# doorduino3.net
KiCad netlist of a schematic drawn in EAGLE
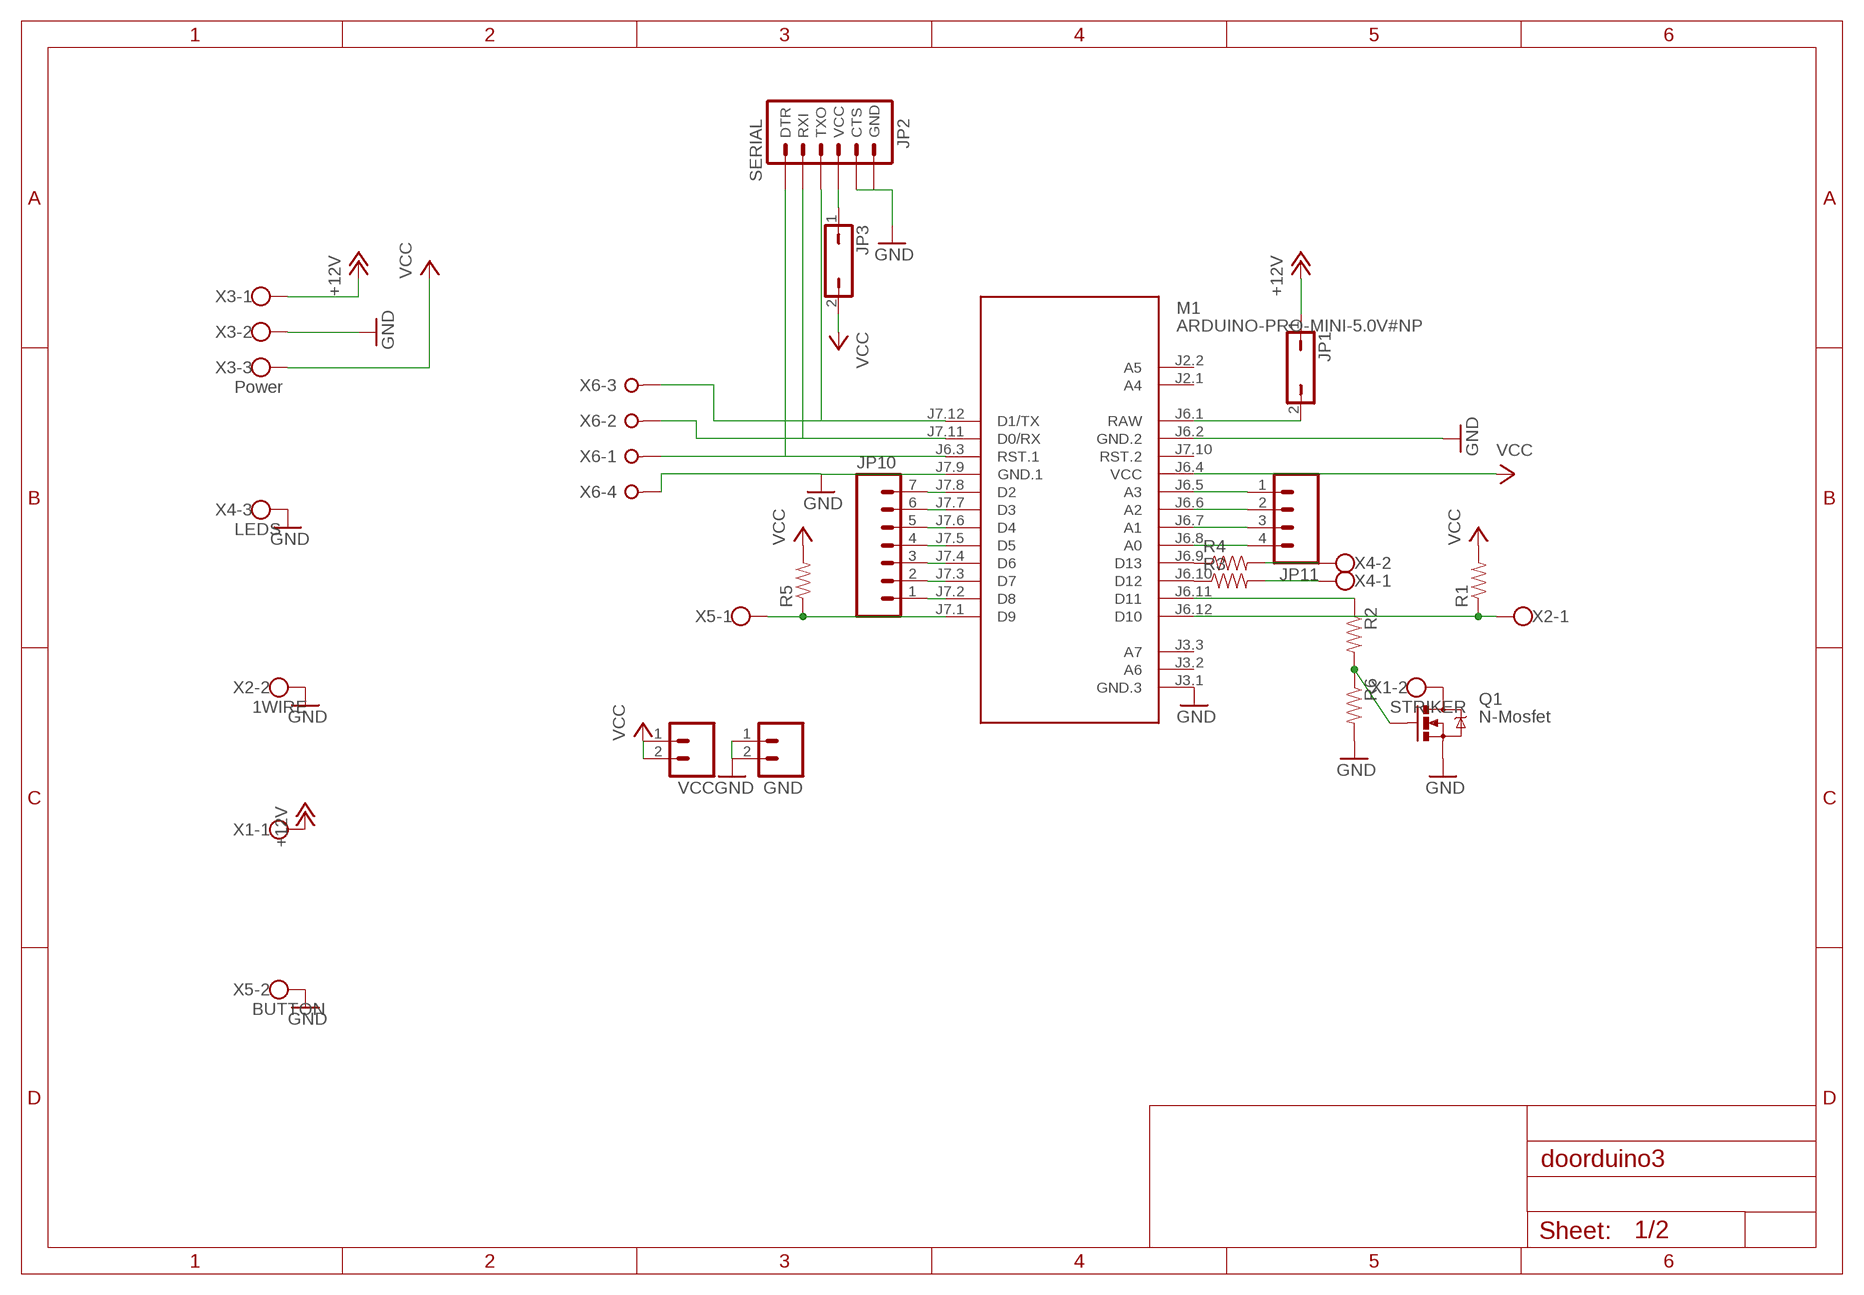
[diagram p0: schematic, sheet 1]
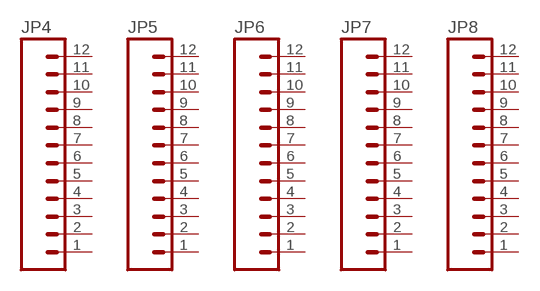
[diagram p1: schematic, sheet 2]

(export (version "E")
  (design (tool "Eeschema 10.0.6"))
  (components
    (comp (ref "JP4")
      (value "M12NO_SILK")
      (footprint "eagle-import:1X12_NO_SILK")
      (libsource (lib "eagle-import") (part "M12NO_SILK"))
    )
    (comp (ref "JP5")
      (value "M12NO_SILK")
      (footprint "eagle-import:1X12_NO_SILK")
      (libsource (lib "eagle-import") (part "M12NO_SILK"))
    )
    (comp (ref "JP6")
      (value "M12NO_SILK")
      (footprint "eagle-import:1X12_NO_SILK")
      (libsource (lib "eagle-import") (part "M12NO_SILK"))
    )
    (comp (ref "JP7")
      (value "M12NO_SILK")
      (footprint "eagle-import:1X12_NO_SILK")
      (libsource (lib "eagle-import") (part "M12NO_SILK"))
    )
    (comp (ref "JP8")
      (value "M12NO_SILK")
      (footprint "eagle-import:1X12_NO_SILK")
      (libsource (lib "eagle-import") (part "M12NO_SILK"))
    )
    (comp (ref "GND")
      (value "M021X02_NO_SILK")
      (footprint "eagle-import:1X02_NO_SILK")
      (libsource (lib "eagle-import") (part "M021X02_NO_SILK"))
    )
    (comp (ref "JP1")
      (value "JP1Q")
      (footprint "eagle-import:JP1")
      (libsource (lib "eagle-import") (part "JP1Q"))
    )
    (comp (ref "JP2")
      (value "SERIAL")
      (footprint "eagle-import:1X06_LONGPADS")
      (libsource (lib "eagle-import") (part "ARDUINO_SERIAL_PROGRAMLONGPADS"))
    )
    (comp (ref "JP3")
      (value "JP1Q")
      (footprint "eagle-import:JP1")
      (libsource (lib "eagle-import") (part "JP1Q"))
    )
    (comp (ref "JP10")
      (value "M07")
      (footprint "eagle-import:1X07")
      (libsource (lib "eagle-import") (part "M07"))
    )
    (comp (ref "JP11")
      (value "M04NO_SILK_ALL_ROUND")
      (footprint "eagle-import:1X04_NO_SILK_ALL_ROUND")
      (libsource (lib "eagle-import") (part "M04NO_SILK_ALL_ROUND"))
    )
    (comp (ref "M1")
      (value "ARDUINO-PRO-MINI-5.0V#NP")
      (footprint "eagle-import:ARDUINO-PRO-MINI#NP")
      (libsource (lib "eagle-import") (part "ARDUINO-PRO-MINI-#NP5.0V"))
    )
    (comp (ref "Q1")
      (value "N-Mosfet")
      (footprint "eagle-import:TO220V")
      (libsource (lib "eagle-import") (part "MOSFET-NCHANNELFQP30N06L"))
    )
    (comp (ref "R1")
      (value "RESISTOR0805-RES")
      (footprint "eagle-import:0805")
      (libsource (lib "eagle-import") (part "RESISTOR0805-RES"))
    )
    (comp (ref "R2")
      (value "RESISTOR0805-RES")
      (footprint "eagle-import:0805")
      (libsource (lib "eagle-import") (part "RESISTOR0805-RES"))
    )
    (comp (ref "R3")
      (value "RESISTOR0805-RES")
      (footprint "eagle-import:0805")
      (libsource (lib "eagle-import") (part "RESISTOR0805-RES"))
    )
    (comp (ref "R4")
      (value "RESISTOR0805-RES")
      (footprint "eagle-import:0805")
      (libsource (lib "eagle-import") (part "RESISTOR0805-RES"))
    )
    (comp (ref "R5")
      (value "RESISTOR0805-RES")
      (footprint "eagle-import:0805")
      (libsource (lib "eagle-import") (part "RESISTOR0805-RES"))
    )
    (comp (ref "R6")
      (value "RESISTOR0805-RES")
      (footprint "eagle-import:0805")
      (libsource (lib "eagle-import") (part "RESISTOR0805-RES"))
    )
    (comp (ref "VCC")
      (value "M021X02_NO_SILK")
      (footprint "eagle-import:1X02_NO_SILK")
      (libsource (lib "eagle-import") (part "M021X02_NO_SILK"))
    )
    (comp (ref "X1")
      (value "STRIKER")
      (footprint "eagle-import:W237-102")
      (fields (field (name "MPN") "237-102"))
      (libsource (lib "eagle-import") (part "W237-102"))
    )
    (comp (ref "X2")
      (value "1WIRE")
      (footprint "eagle-import:W237-102")
      (fields (field (name "MPN") "237-102"))
      (libsource (lib "eagle-import") (part "W237-102"))
    )
    (comp (ref "X3")
      (value "Power")
      (footprint "eagle-import:W237-103")
      (fields (field (name "MPN") "237-103"))
      (libsource (lib "eagle-import") (part "W237-103"))
    )
    (comp (ref "X4")
      (value "LEDS")
      (footprint "eagle-import:W237-103")
      (fields (field (name "MPN") "237-103"))
      (libsource (lib "eagle-import") (part "W237-103"))
    )
    (comp (ref "X5")
      (value "BUTTON")
      (footprint "eagle-import:W237-102")
      (fields (field (name "MPN") "237-102"))
      (libsource (lib "eagle-import") (part "W237-102"))
    )
    (comp (ref "X6")
      (value "W237-04P")
      (footprint "eagle-import:W237-4P")
      (libsource (lib "eagle-import") (part "W237-04P"))
    )
  )
  (nets
    (net (code "1") (name "+12V") (class "Default")
      (node (ref "JP1") (pin "1") (pinfunction "1_1") (pintype "passive"))
      (node (ref "X1") (pin "1") (pinfunction "KL_1") (pintype "passive"))
      (node (ref "X3") (pin "1") (pinfunction "KL_1") (pintype "passive"))
    )
    (net (code "2") (name "GND") (class "Default")
      (node (ref "GND") (pin "1") (pinfunction "1_1") (pintype "passive"))
      (node (ref "GND") (pin "2") (pinfunction "2_2") (pintype "passive"))
      (node (ref "JP2") (pin "5") (pinfunction "CTS_5") (pintype "passive"))
      (node (ref "JP2") (pin "6") (pinfunction "GND_6") (pintype "passive"))
      (node (ref "M1") (pin "J3.1") (pinfunction "GND.3_J3.1") (pintype "bidirectional"))
      (node (ref "M1") (pin "J6.2") (pinfunction "GND.2_J6.2") (pintype "power_in"))
      (node (ref "M1") (pin "J7.9") (pinfunction "GND.1_J7.9") (pintype "power_in"))
      (node (ref "Q1") (pin "3") (pinfunction "S_3") (pintype "passive"))
      (node (ref "R6") (pin "2") (pinfunction "2_2") (pintype "passive"))
      (node (ref "X2") (pin "2") (pinfunction "KL_2") (pintype "passive"))
      (node (ref "X3") (pin "2") (pinfunction "KL_2") (pintype "passive"))
      (node (ref "X4") (pin "3") (pinfunction "KL_3") (pintype "passive"))
      (node (ref "X5") (pin "2") (pinfunction "KL_2") (pintype "passive"))
      (node (ref "X6") (pin "4") (pinfunction "KL_4") (pintype "passive"))
    )
    (net (code "3") (name "Net-(JP2-DTR)") (class "Default")
      (node (ref "JP2") (pin "1") (pinfunction "DTR_1") (pintype "passive"))
      (node (ref "M1") (pin "J6.3") (pinfunction "RST.1_J6.3") (pintype "bidirectional"))
      (node (ref "X6") (pin "1") (pinfunction "KL_1") (pintype "passive"))
    )
    (net (code "4") (name "Net-(JP2-RXI)") (class "Default")
      (node (ref "JP2") (pin "2") (pinfunction "RXI_2") (pintype "passive"))
      (node (ref "M1") (pin "J7.11") (pinfunction "D0/RX_J7.11") (pintype "bidirectional"))
      (node (ref "X6") (pin "2") (pinfunction "KL_2") (pintype "passive"))
    )
    (net (code "5") (name "Net-(JP2-TXO)") (class "Default")
      (node (ref "JP2") (pin "3") (pinfunction "TXO_3") (pintype "passive"))
      (node (ref "M1") (pin "J7.12") (pinfunction "D1/TX_J7.12") (pintype "bidirectional"))
      (node (ref "X6") (pin "3") (pinfunction "KL_3") (pintype "passive"))
    )
    (net (code "6") (name "Net-(JP2-VCC)") (class "Default")
      (node (ref "JP2") (pin "4") (pinfunction "VCC_4") (pintype "passive"))
      (node (ref "JP3") (pin "1") (pinfunction "1_1") (pintype "passive"))
    )
    (net (code "7") (name "Net-(M1-A0)") (class "Default")
      (node (ref "JP11") (pin "4") (pinfunction "4_4") (pintype "passive"))
      (node (ref "M1") (pin "J6.8") (pinfunction "A0_J6.8") (pintype "bidirectional"))
    )
    (net (code "8") (name "Net-(M1-A1)") (class "Default")
      (node (ref "JP11") (pin "3") (pinfunction "3_3") (pintype "passive"))
      (node (ref "M1") (pin "J6.7") (pinfunction "A1_J6.7") (pintype "bidirectional"))
    )
    (net (code "9") (name "Net-(M1-A2)") (class "Default")
      (node (ref "JP11") (pin "2") (pinfunction "2_2") (pintype "passive"))
      (node (ref "M1") (pin "J6.6") (pinfunction "A2_J6.6") (pintype "bidirectional"))
    )
    (net (code "10") (name "Net-(M1-A3)") (class "Default")
      (node (ref "JP11") (pin "1") (pinfunction "1_1") (pintype "passive"))
      (node (ref "M1") (pin "J6.5") (pinfunction "A3_J6.5") (pintype "bidirectional"))
    )
    (net (code "11") (name "Net-(M1-D2)") (class "Default")
      (node (ref "JP10") (pin "7") (pinfunction "7_7") (pintype "passive"))
      (node (ref "M1") (pin "J7.8") (pinfunction "D2_J7.8") (pintype "bidirectional"))
    )
    (net (code "12") (name "Net-(M1-D3)") (class "Default")
      (node (ref "JP10") (pin "6") (pinfunction "6_6") (pintype "passive"))
      (node (ref "M1") (pin "J7.7") (pinfunction "D3_J7.7") (pintype "bidirectional"))
    )
    (net (code "13") (name "Net-(M1-D4)") (class "Default")
      (node (ref "JP10") (pin "5") (pinfunction "5_5") (pintype "passive"))
      (node (ref "M1") (pin "J7.6") (pinfunction "D4_J7.6") (pintype "bidirectional"))
    )
    (net (code "14") (name "Net-(M1-D5)") (class "Default")
      (node (ref "JP10") (pin "4") (pinfunction "4_4") (pintype "passive"))
      (node (ref "M1") (pin "J7.5") (pinfunction "D5_J7.5") (pintype "bidirectional"))
    )
    (net (code "15") (name "Net-(M1-D6)") (class "Default")
      (node (ref "JP10") (pin "3") (pinfunction "3_3") (pintype "passive"))
      (node (ref "M1") (pin "J7.4") (pinfunction "D6_J7.4") (pintype "bidirectional"))
    )
    (net (code "16") (name "Net-(M1-D7)") (class "Default")
      (node (ref "JP10") (pin "2") (pinfunction "2_2") (pintype "passive"))
      (node (ref "M1") (pin "J7.3") (pinfunction "D7_J7.3") (pintype "bidirectional"))
    )
    (net (code "17") (name "Net-(M1-D8)") (class "Default")
      (node (ref "JP10") (pin "1") (pinfunction "1_1") (pintype "passive"))
      (node (ref "M1") (pin "J7.2") (pinfunction "D8_J7.2") (pintype "bidirectional"))
    )
    (net (code "18") (name "Net-(M1-D9)") (class "Default")
      (node (ref "M1") (pin "J7.1") (pinfunction "D9_J7.1") (pintype "bidirectional"))
      (node (ref "R5") (pin "1") (pinfunction "1_1") (pintype "passive"))
      (node (ref "X5") (pin "1") (pinfunction "KL_1") (pintype "passive"))
    )
    (net (code "19") (name "Net-(M1-D10)") (class "Default")
      (node (ref "M1") (pin "J6.12") (pinfunction "D10_J6.12") (pintype "bidirectional"))
      (node (ref "R1") (pin "1") (pinfunction "1_1") (pintype "passive"))
      (node (ref "X2") (pin "1") (pinfunction "KL_1") (pintype "passive"))
    )
    (net (code "20") (name "Net-(M1-D11)") (class "Default")
      (node (ref "M1") (pin "J6.11") (pinfunction "D11_J6.11") (pintype "bidirectional"))
      (node (ref "R2") (pin "1") (pinfunction "1_1") (pintype "passive"))
    )
    (net (code "21") (name "Net-(M1-D12)") (class "Default")
      (node (ref "M1") (pin "J6.10") (pinfunction "D12_J6.10") (pintype "bidirectional"))
      (node (ref "R3") (pin "1") (pinfunction "1_1") (pintype "passive"))
    )
    (net (code "22") (name "Net-(M1-D13)") (class "Default")
      (node (ref "M1") (pin "J6.9") (pinfunction "D13_J6.9") (pintype "bidirectional"))
      (node (ref "R4") (pin "1") (pinfunction "1_1") (pintype "passive"))
    )
    (net (code "23") (name "Net-(M1-RAW)") (class "Default")
      (node (ref "JP1") (pin "2") (pinfunction "2_2") (pintype "passive"))
      (node (ref "M1") (pin "J6.1") (pinfunction "RAW_J6.1") (pintype "power_in"))
    )
    (net (code "24") (name "Net-(Q1-D)") (class "Default")
      (node (ref "Q1") (pin "2") (pinfunction "D_2") (pintype "passive"))
      (node (ref "X1") (pin "2") (pinfunction "KL_2") (pintype "passive"))
    )
    (net (code "25") (name "Net-(Q1-G)") (class "Default")
      (node (ref "Q1") (pin "1") (pinfunction "G_1") (pintype "passive"))
      (node (ref "R2") (pin "2") (pinfunction "2_2") (pintype "passive"))
      (node (ref "R6") (pin "1") (pinfunction "1_1") (pintype "passive"))
    )
    (net (code "26") (name "Net-(X4A-KL)") (class "Default")
      (node (ref "R3") (pin "2") (pinfunction "2_2") (pintype "passive"))
      (node (ref "X4") (pin "1") (pinfunction "KL_1") (pintype "passive"))
    )
    (net (code "27") (name "Net-(X4B-KL)") (class "Default")
      (node (ref "R4") (pin "2") (pinfunction "2_2") (pintype "passive"))
      (node (ref "X4") (pin "2") (pinfunction "KL_2") (pintype "passive"))
    )
    (net (code "28") (name "VCC") (class "Default")
      (node (ref "JP3") (pin "2") (pinfunction "2_2") (pintype "passive"))
      (node (ref "M1") (pin "J6.4") (pinfunction "VCC_J6.4") (pintype "power_in"))
      (node (ref "R1") (pin "2") (pinfunction "2_2") (pintype "passive"))
      (node (ref "R5") (pin "2") (pinfunction "2_2") (pintype "passive"))
      (node (ref "VCC") (pin "1") (pinfunction "1_1") (pintype "passive"))
      (node (ref "VCC") (pin "2") (pinfunction "2_2") (pintype "passive"))
      (node (ref "X3") (pin "3") (pinfunction "KL_3") (pintype "passive"))
    )
    (net (code "29") (name "unconnected-(JP4-Pad1)") (class "Default")
      (node (ref "JP4") (pin "1") (pinfunction "1_1") (pintype "passive"))
    )
    (net (code "30") (name "unconnected-(JP4-Pad2)") (class "Default")
      (node (ref "JP4") (pin "2") (pinfunction "2_2") (pintype "passive"))
    )
    (net (code "31") (name "unconnected-(JP4-Pad3)") (class "Default")
      (node (ref "JP4") (pin "3") (pinfunction "3_3") (pintype "passive"))
    )
    (net (code "32") (name "unconnected-(JP4-Pad4)") (class "Default")
      (node (ref "JP4") (pin "4") (pinfunction "4_4") (pintype "passive"))
    )
    (net (code "33") (name "unconnected-(JP4-Pad5)") (class "Default")
      (node (ref "JP4") (pin "5") (pinfunction "5_5") (pintype "passive"))
    )
    (net (code "34") (name "unconnected-(JP4-Pad6)") (class "Default")
      (node (ref "JP4") (pin "6") (pinfunction "6_6") (pintype "passive"))
    )
    (net (code "35") (name "unconnected-(JP4-Pad7)") (class "Default")
      (node (ref "JP4") (pin "7") (pinfunction "7_7") (pintype "passive"))
    )
    (net (code "36") (name "unconnected-(JP4-Pad8)") (class "Default")
      (node (ref "JP4") (pin "8") (pinfunction "8_8") (pintype "passive"))
    )
    (net (code "37") (name "unconnected-(JP4-Pad9)") (class "Default")
      (node (ref "JP4") (pin "9") (pinfunction "9_9") (pintype "passive"))
    )
    (net (code "38") (name "unconnected-(JP4-Pad10)") (class "Default")
      (node (ref "JP4") (pin "10") (pinfunction "10_10") (pintype "passive"))
    )
    (net (code "39") (name "unconnected-(JP4-Pad11)") (class "Default")
      (node (ref "JP4") (pin "11") (pinfunction "11_11") (pintype "passive"))
    )
    (net (code "40") (name "unconnected-(JP4-Pad12)") (class "Default")
      (node (ref "JP4") (pin "12") (pinfunction "12_12") (pintype "passive"))
    )
    (net (code "41") (name "unconnected-(JP5-Pad1)") (class "Default")
      (node (ref "JP5") (pin "1") (pinfunction "1_1") (pintype "passive"))
    )
    (net (code "42") (name "unconnected-(JP5-Pad2)") (class "Default")
      (node (ref "JP5") (pin "2") (pinfunction "2_2") (pintype "passive"))
    )
    (net (code "43") (name "unconnected-(JP5-Pad3)") (class "Default")
      (node (ref "JP5") (pin "3") (pinfunction "3_3") (pintype "passive"))
    )
    (net (code "44") (name "unconnected-(JP5-Pad4)") (class "Default")
      (node (ref "JP5") (pin "4") (pinfunction "4_4") (pintype "passive"))
    )
    (net (code "45") (name "unconnected-(JP5-Pad5)") (class "Default")
      (node (ref "JP5") (pin "5") (pinfunction "5_5") (pintype "passive"))
    )
    (net (code "46") (name "unconnected-(JP5-Pad6)") (class "Default")
      (node (ref "JP5") (pin "6") (pinfunction "6_6") (pintype "passive"))
    )
    (net (code "47") (name "unconnected-(JP5-Pad7)") (class "Default")
      (node (ref "JP5") (pin "7") (pinfunction "7_7") (pintype "passive"))
    )
    (net (code "48") (name "unconnected-(JP5-Pad8)") (class "Default")
      (node (ref "JP5") (pin "8") (pinfunction "8_8") (pintype "passive"))
    )
    (net (code "49") (name "unconnected-(JP5-Pad9)") (class "Default")
      (node (ref "JP5") (pin "9") (pinfunction "9_9") (pintype "passive"))
    )
    (net (code "50") (name "unconnected-(JP5-Pad10)") (class "Default")
      (node (ref "JP5") (pin "10") (pinfunction "10_10") (pintype "passive"))
    )
    (net (code "51") (name "unconnected-(JP5-Pad11)") (class "Default")
      (node (ref "JP5") (pin "11") (pinfunction "11_11") (pintype "passive"))
    )
    (net (code "52") (name "unconnected-(JP5-Pad12)") (class "Default")
      (node (ref "JP5") (pin "12") (pinfunction "12_12") (pintype "passive"))
    )
    (net (code "53") (name "unconnected-(JP6-Pad1)") (class "Default")
      (node (ref "JP6") (pin "1") (pinfunction "1_1") (pintype "passive"))
    )
    (net (code "54") (name "unconnected-(JP6-Pad2)") (class "Default")
      (node (ref "JP6") (pin "2") (pinfunction "2_2") (pintype "passive"))
    )
    (net (code "55") (name "unconnected-(JP6-Pad3)") (class "Default")
      (node (ref "JP6") (pin "3") (pinfunction "3_3") (pintype "passive"))
    )
    (net (code "56") (name "unconnected-(JP6-Pad4)") (class "Default")
      (node (ref "JP6") (pin "4") (pinfunction "4_4") (pintype "passive"))
    )
    (net (code "57") (name "unconnected-(JP6-Pad5)") (class "Default")
      (node (ref "JP6") (pin "5") (pinfunction "5_5") (pintype "passive"))
    )
    (net (code "58") (name "unconnected-(JP6-Pad6)") (class "Default")
      (node (ref "JP6") (pin "6") (pinfunction "6_6") (pintype "passive"))
    )
    (net (code "59") (name "unconnected-(JP6-Pad7)") (class "Default")
      (node (ref "JP6") (pin "7") (pinfunction "7_7") (pintype "passive"))
    )
    (net (code "60") (name "unconnected-(JP6-Pad8)") (class "Default")
      (node (ref "JP6") (pin "8") (pinfunction "8_8") (pintype "passive"))
    )
    (net (code "61") (name "unconnected-(JP6-Pad9)") (class "Default")
      (node (ref "JP6") (pin "9") (pinfunction "9_9") (pintype "passive"))
    )
    (net (code "62") (name "unconnected-(JP6-Pad10)") (class "Default")
      (node (ref "JP6") (pin "10") (pinfunction "10_10") (pintype "passive"))
    )
    (net (code "63") (name "unconnected-(JP6-Pad11)") (class "Default")
      (node (ref "JP6") (pin "11") (pinfunction "11_11") (pintype "passive"))
    )
    (net (code "64") (name "unconnected-(JP6-Pad12)") (class "Default")
      (node (ref "JP6") (pin "12") (pinfunction "12_12") (pintype "passive"))
    )
    (net (code "65") (name "unconnected-(JP7-Pad1)") (class "Default")
      (node (ref "JP7") (pin "1") (pinfunction "1_1") (pintype "passive"))
    )
    (net (code "66") (name "unconnected-(JP7-Pad2)") (class "Default")
      (node (ref "JP7") (pin "2") (pinfunction "2_2") (pintype "passive"))
    )
    (net (code "67") (name "unconnected-(JP7-Pad3)") (class "Default")
      (node (ref "JP7") (pin "3") (pinfunction "3_3") (pintype "passive"))
    )
    (net (code "68") (name "unconnected-(JP7-Pad4)") (class "Default")
      (node (ref "JP7") (pin "4") (pinfunction "4_4") (pintype "passive"))
    )
    (net (code "69") (name "unconnected-(JP7-Pad5)") (class "Default")
      (node (ref "JP7") (pin "5") (pinfunction "5_5") (pintype "passive"))
    )
    (net (code "70") (name "unconnected-(JP7-Pad6)") (class "Default")
      (node (ref "JP7") (pin "6") (pinfunction "6_6") (pintype "passive"))
    )
    (net (code "71") (name "unconnected-(JP7-Pad7)") (class "Default")
      (node (ref "JP7") (pin "7") (pinfunction "7_7") (pintype "passive"))
    )
    (net (code "72") (name "unconnected-(JP7-Pad8)") (class "Default")
      (node (ref "JP7") (pin "8") (pinfunction "8_8") (pintype "passive"))
    )
    (net (code "73") (name "unconnected-(JP7-Pad9)") (class "Default")
      (node (ref "JP7") (pin "9") (pinfunction "9_9") (pintype "passive"))
    )
    (net (code "74") (name "unconnected-(JP7-Pad10)") (class "Default")
      (node (ref "JP7") (pin "10") (pinfunction "10_10") (pintype "passive"))
    )
    (net (code "75") (name "unconnected-(JP7-Pad11)") (class "Default")
      (node (ref "JP7") (pin "11") (pinfunction "11_11") (pintype "passive"))
    )
    (net (code "76") (name "unconnected-(JP7-Pad12)") (class "Default")
      (node (ref "JP7") (pin "12") (pinfunction "12_12") (pintype "passive"))
    )
    (net (code "77") (name "unconnected-(JP8-Pad1)") (class "Default")
      (node (ref "JP8") (pin "1") (pinfunction "1_1") (pintype "passive"))
    )
    (net (code "78") (name "unconnected-(JP8-Pad2)") (class "Default")
      (node (ref "JP8") (pin "2") (pinfunction "2_2") (pintype "passive"))
    )
    (net (code "79") (name "unconnected-(JP8-Pad3)") (class "Default")
      (node (ref "JP8") (pin "3") (pinfunction "3_3") (pintype "passive"))
    )
    (net (code "80") (name "unconnected-(JP8-Pad4)") (class "Default")
      (node (ref "JP8") (pin "4") (pinfunction "4_4") (pintype "passive"))
    )
    (net (code "81") (name "unconnected-(JP8-Pad5)") (class "Default")
      (node (ref "JP8") (pin "5") (pinfunction "5_5") (pintype "passive"))
    )
    (net (code "82") (name "unconnected-(JP8-Pad6)") (class "Default")
      (node (ref "JP8") (pin "6") (pinfunction "6_6") (pintype "passive"))
    )
    (net (code "83") (name "unconnected-(JP8-Pad7)") (class "Default")
      (node (ref "JP8") (pin "7") (pinfunction "7_7") (pintype "passive"))
    )
    (net (code "84") (name "unconnected-(JP8-Pad8)") (class "Default")
      (node (ref "JP8") (pin "8") (pinfunction "8_8") (pintype "passive"))
    )
    (net (code "85") (name "unconnected-(JP8-Pad9)") (class "Default")
      (node (ref "JP8") (pin "9") (pinfunction "9_9") (pintype "passive"))
    )
    (net (code "86") (name "unconnected-(JP8-Pad10)") (class "Default")
      (node (ref "JP8") (pin "10") (pinfunction "10_10") (pintype "passive"))
    )
    (net (code "87") (name "unconnected-(JP8-Pad11)") (class "Default")
      (node (ref "JP8") (pin "11") (pinfunction "11_11") (pintype "passive"))
    )
    (net (code "88") (name "unconnected-(JP8-Pad12)") (class "Default")
      (node (ref "JP8") (pin "12") (pinfunction "12_12") (pintype "passive"))
    )
    (net (code "89") (name "unconnected-(M1-A4-PadJ2.1)") (class "Default")
      (node (ref "M1") (pin "J2.1") (pinfunction "A4_J2.1") (pintype "bidirectional"))
    )
    (net (code "90") (name "unconnected-(M1-A5-PadJ2.2)") (class "Default")
      (node (ref "M1") (pin "J2.2") (pinfunction "A5_J2.2") (pintype "bidirectional"))
    )
    (net (code "91") (name "unconnected-(M1-A6-PadJ3.2)") (class "Default")
      (node (ref "M1") (pin "J3.2") (pinfunction "A6_J3.2") (pintype "bidirectional"))
    )
    (net (code "92") (name "unconnected-(M1-A7-PadJ3.3)") (class "Default")
      (node (ref "M1") (pin "J3.3") (pinfunction "A7_J3.3") (pintype "bidirectional"))
    )
    (net (code "93") (name "unconnected-(M1-RST.2-PadJ7.10)") (class "Default")
      (node (ref "M1") (pin "J7.10") (pinfunction "RST.2_J7.10") (pintype "bidirectional"))
    )
  )
)
